# gate_wifi__bottom.net
KiCad netlist of a schematic drawn in EAGLE
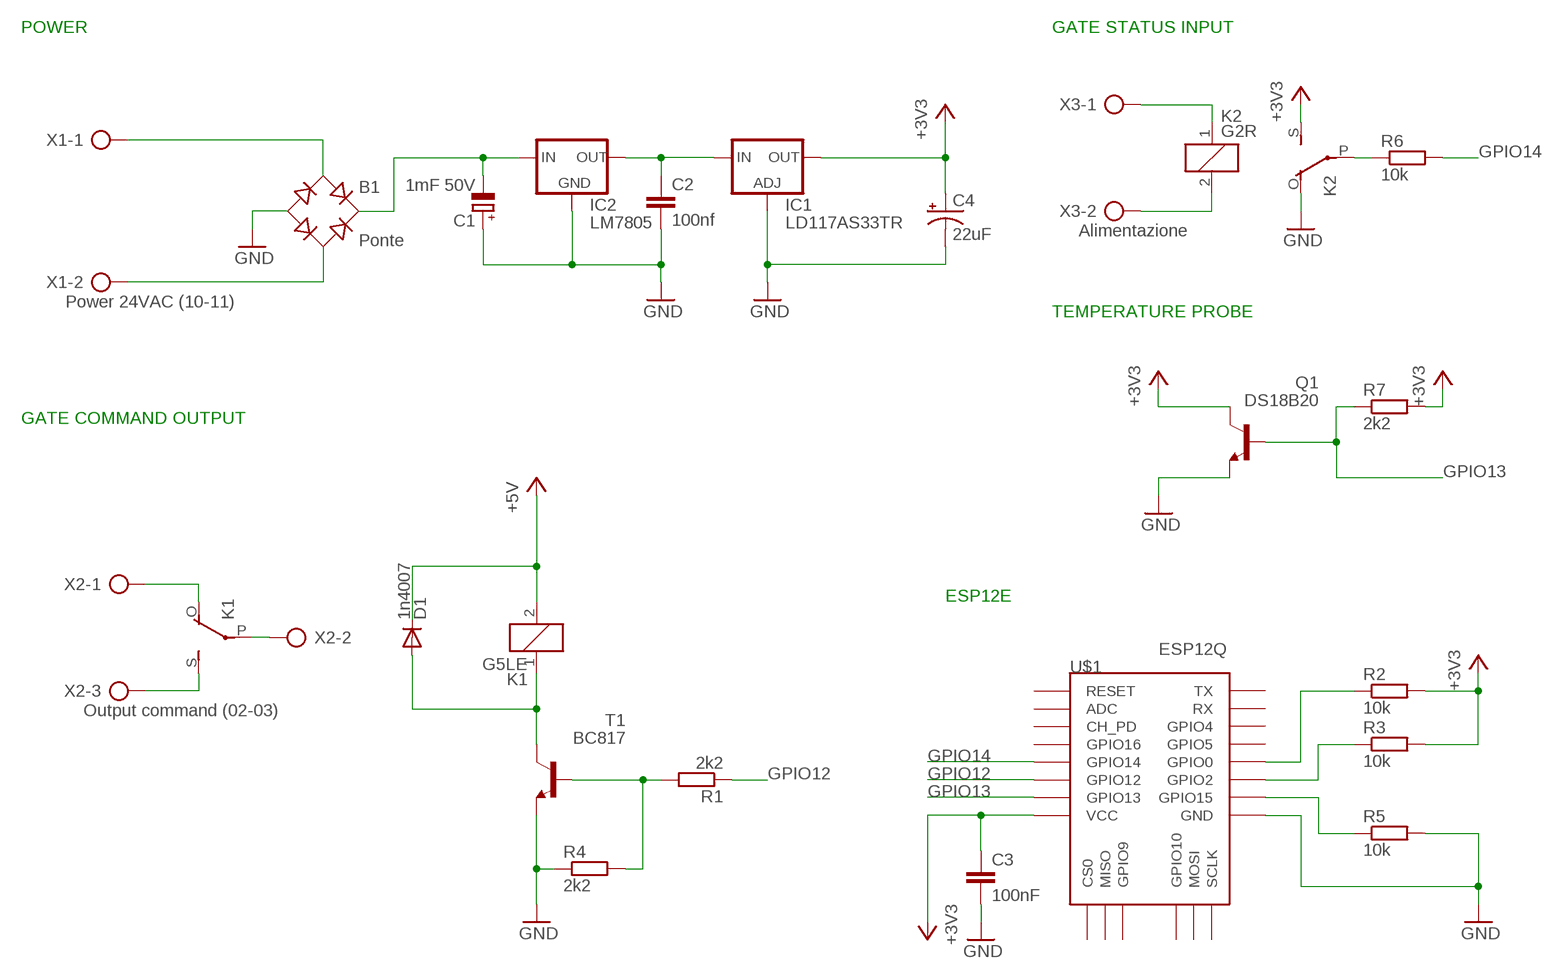
[diagram p0: schematic, sheet 1]

(export (version "E")
  (design (tool "Eeschema 10.0.6"))
  (components
    (comp (ref "B1")
      (value "Ponte")
      (footprint "eagle-import:RB1A_MOD")
      (libsource (lib "eagle-import") (part "RB1A_MODMOD"))
    )
    (comp (ref "C1")
      (value "1mF 50V")
      (footprint "eagle-import:E5-8,5")
      (libsource (lib "eagle-import") (part "CPOL-EUE5-8.5"))
    )
    (comp (ref "C2")
      (value "100nf")
      (footprint "eagle-import:C0805K")
      (libsource (lib "eagle-import") (part "C-EUC0805K"))
    )
    (comp (ref "C3")
      (value "100nF")
      (footprint "eagle-import:C0805K")
      (libsource (lib "eagle-import") (part "C-EUC0805K"))
    )
    (comp (ref "C4")
      (value "22uF")
      (footprint "eagle-import:E2,5-5")
      (libsource (lib "eagle-import") (part "CPOL-USE2.5-5"))
    )
    (comp (ref "D1")
      (value "1n4007")
      (footprint "eagle-import:DO-214AC")
      (libsource (lib "eagle-import") (part "DIODE-DO-214AC"))
    )
    (comp (ref "IC1")
      (value "LD117AS33TR")
      (footprint "eagle-import:SOT223")
      (libsource (lib "eagle-import") (part "LD117A?S33TR"))
    )
    (comp (ref "IC2")
      (value "LM7805")
      (footprint "eagle-import:78XXS")
      (libsource (lib "eagle-import") (part "78XXS"))
    )
    (comp (ref "K1")
      (value "G5LE")
      (footprint "eagle-import:G5LE")
      (libsource (lib "eagle-import") (part "G5LE"))
    )
    (comp (ref "K2")
      (value "G2R")
      (footprint "eagle-import:G2R")
      (libsource (lib "eagle-import") (part "G2R"))
    )
    (comp (ref "Q1")
      (value "DS18B20")
      (footprint "eagle-import:TO92")
      (libsource (lib "eagle-import") (part "2N3565"))
    )
    (comp (ref "R1")
      (value "2k2")
      (footprint "eagle-import:M0805")
      (libsource (lib "eagle-import") (part "R-EU_M0805"))
    )
    (comp (ref "R2")
      (value "10k")
      (footprint "eagle-import:M0805")
      (libsource (lib "eagle-import") (part "R-EU_M0805"))
    )
    (comp (ref "R3")
      (value "10k")
      (footprint "eagle-import:M0805")
      (libsource (lib "eagle-import") (part "R-EU_M0805"))
    )
    (comp (ref "R4")
      (value "2k2")
      (footprint "eagle-import:M0805")
      (libsource (lib "eagle-import") (part "R-EU_M0805"))
    )
    (comp (ref "R5")
      (value "10k")
      (footprint "eagle-import:M0805")
      (libsource (lib "eagle-import") (part "R-EU_M0805"))
    )
    (comp (ref "R6")
      (value "10k")
      (footprint "eagle-import:M0805")
      (libsource (lib "eagle-import") (part "R-EU_M0805"))
    )
    (comp (ref "R7")
      (value "2k2")
      (footprint "eagle-import:M0805")
      (libsource (lib "eagle-import") (part "R-EU_M0805"))
    )
    (comp (ref "T1")
      (value "BC817")
      (footprint "eagle-import:SOT23-BEC")
      (libsource (lib "eagle-import") (part "-NPN-SOT23-BECBC817-16LT1"))
    )
    (comp (ref "U$1")
      (value "ESP12Q")
      (footprint "eagle-import:ESP12Q")
      (libsource (lib "eagle-import") (part "ESP12Q"))
    )
    (comp (ref "X1")
      (value "Power 24VAC (10-11)")
      (footprint "eagle-import:AK500_2")
      (libsource (lib "eagle-import") (part "AK500/2"))
    )
    (comp (ref "X2")
      (value "Output command (02-03)")
      (footprint "eagle-import:AK500_3")
      (libsource (lib "eagle-import") (part "AK500/3"))
    )
    (comp (ref "X3")
      (value "Alimentazione")
      (footprint "eagle-import:AK500_2")
      (libsource (lib "eagle-import") (part "AK500/2"))
    )
  )
  (nets
    (net (code "1") (name "+3V3") (class "Default")
      (node (ref "C3") (pin "1") (pinfunction "1_1") (pintype "passive"))
      (node (ref "C4") (pin "+") (pinfunction "+_+") (pintype "passive"))
      (node (ref "IC1") (pin "4") (pinfunction "OUT_4") (pintype "passive"))
      (node (ref "K2") (pin "S") (pinfunction "S_S") (pintype "passive"))
      (node (ref "Q1") (pin "1") (pinfunction "C_1") (pintype "passive"))
      (node (ref "R2") (pin "2") (pinfunction "2_2") (pintype "passive"))
      (node (ref "R3") (pin "2") (pinfunction "2_2") (pintype "passive"))
      (node (ref "R7") (pin "2") (pinfunction "2_2") (pintype "passive"))
      (node (ref "U$1") (pin "VCC") (pinfunction "VCC_VCC") (pintype "bidirectional"))
    )
    (net (code "2") (name "+5V") (class "Default")
      (node (ref "D1") (pin "C") (pinfunction "C_C") (pintype "passive"))
      (node (ref "K1") (pin "2") (pinfunction "2_2") (pintype "passive"))
    )
    (net (code "3") (name "/GPIO12") (class "Default")
      (node (ref "R1") (pin "1") (pinfunction "1_1") (pintype "passive"))
      (node (ref "U$1") (pin "GPIO12") (pinfunction "GPIO12_GPIO12") (pintype "bidirectional"))
    )
    (net (code "4") (name "/GPIO13") (class "Default")
      (node (ref "Q1") (pin "2") (pinfunction "B_2") (pintype "passive"))
      (node (ref "R7") (pin "1") (pinfunction "1_1") (pintype "passive"))
      (node (ref "U$1") (pin "GPIO13") (pinfunction "GPIO13_GPIO13") (pintype "bidirectional"))
    )
    (net (code "5") (name "/GPIO14") (class "Default")
      (node (ref "R6") (pin "2") (pinfunction "2_2") (pintype "passive"))
      (node (ref "U$1") (pin "GPIO14") (pinfunction "GPIO14_GPIO14") (pintype "bidirectional"))
    )
    (net (code "6") (name "GND") (class "Default")
      (node (ref "B1") (pin "-") (pinfunction "-_-") (pintype "passive"))
      (node (ref "C1") (pin "+") (pinfunction "+_+") (pintype "passive"))
      (node (ref "C2") (pin "2") (pinfunction "2_2") (pintype "passive"))
      (node (ref "C3") (pin "2") (pinfunction "2_2") (pintype "passive"))
      (node (ref "C4") (pin "-") (pinfunction "-_-") (pintype "passive"))
      (node (ref "IC1") (pin "1") (pinfunction "ADJ_1") (pintype "input"))
      (node (ref "IC2") (pin "GND") (pinfunction "GND_GND") (pintype "input"))
      (node (ref "K2") (pin "O") (pinfunction "O_O") (pintype "passive"))
      (node (ref "Q1") (pin "3") (pinfunction "E_3") (pintype "passive"))
      (node (ref "R4") (pin "1") (pinfunction "1_1") (pintype "passive"))
      (node (ref "R5") (pin "2") (pinfunction "2_2") (pintype "passive"))
      (node (ref "T1") (pin "E") (pinfunction "E_E") (pintype "passive"))
      (node (ref "U$1") (pin "GND") (pinfunction "GND_GND") (pintype "bidirectional"))
    )
    (net (code "7") (name "Net-(B1-Pad+)") (class "Default")
      (node (ref "B1") (pin "+") (pinfunction "+_+") (pintype "passive"))
      (node (ref "C1") (pin "-") (pinfunction "-_-") (pintype "passive"))
      (node (ref "IC2") (pin "IN") (pinfunction "IN_IN") (pintype "input"))
    )
    (net (code "8") (name "Net-(D1-PadA)") (class "Default")
      (node (ref "D1") (pin "A") (pinfunction "A_A") (pintype "passive"))
      (node (ref "K1") (pin "1") (pinfunction "1_1") (pintype "passive"))
      (node (ref "T1") (pin "C") (pinfunction "C_C") (pintype "passive"))
    )
    (net (code "9") (name "Net-(IC1-IN)") (class "Default")
      (node (ref "C2") (pin "1") (pinfunction "1_1") (pintype "passive"))
      (node (ref "IC1") (pin "3") (pinfunction "IN_3") (pintype "input"))
      (node (ref "IC2") (pin "OUT") (pinfunction "OUT_OUT") (pintype "passive"))
    )
    (net (code "10") (name "Net-(K2-PadP)") (class "Default")
      (node (ref "K2") (pin "P") (pinfunction "P_P") (pintype "passive"))
      (node (ref "R6") (pin "1") (pinfunction "1_1") (pintype "passive"))
    )
    (net (code "11") (name "Net-(R1-Pad2)") (class "Default")
      (node (ref "R1") (pin "2") (pinfunction "2_2") (pintype "passive"))
      (node (ref "R4") (pin "2") (pinfunction "2_2") (pintype "passive"))
      (node (ref "T1") (pin "B") (pinfunction "B_B") (pintype "passive"))
    )
    (net (code "12") (name "Net-(R2-Pad1)") (class "Default")
      (node (ref "R2") (pin "1") (pinfunction "1_1") (pintype "passive"))
      (node (ref "U$1") (pin "GPIO0") (pinfunction "GPIO0_GPIO0") (pintype "bidirectional"))
    )
    (net (code "13") (name "Net-(R3-Pad1)") (class "Default")
      (node (ref "R3") (pin "1") (pinfunction "1_1") (pintype "passive"))
      (node (ref "U$1") (pin "GPIO2") (pinfunction "GPIO2_GPIO2") (pintype "bidirectional"))
    )
    (net (code "14") (name "Net-(R5-Pad1)") (class "Default")
      (node (ref "R5") (pin "1") (pinfunction "1_1") (pintype "passive"))
      (node (ref "U$1") (pin "GPIO15") (pinfunction "GPIO15_GPIO15") (pintype "bidirectional"))
    )
    (net (code "15") (name "Net-(X1A-KL)") (class "Default")
      (node (ref "B1") (pin "AC1") (pinfunction "AC1_AC1") (pintype "passive"))
      (node (ref "X1") (pin "1") (pinfunction "KL_1") (pintype "passive"))
    )
    (net (code "16") (name "Net-(X1B-KL)") (class "Default")
      (node (ref "B1") (pin "AC2") (pinfunction "AC2_AC2") (pintype "passive"))
      (node (ref "X1") (pin "2") (pinfunction "KL_2") (pintype "passive"))
    )
    (net (code "17") (name "Net-(X2A-KL)") (class "Default")
      (node (ref "K1") (pin "O") (pinfunction "O_O") (pintype "passive"))
      (node (ref "X2") (pin "1") (pinfunction "KL_1") (pintype "passive"))
    )
    (net (code "18") (name "Net-(X2B-KL)") (class "Default")
      (node (ref "K1") (pin "P") (pinfunction "P_P") (pintype "passive"))
      (node (ref "X2") (pin "2") (pinfunction "KL_2") (pintype "passive"))
    )
    (net (code "19") (name "Net-(X2C-KL)") (class "Default")
      (node (ref "K1") (pin "S") (pinfunction "S_S") (pintype "passive"))
      (node (ref "X2") (pin "3") (pinfunction "KL_3") (pintype "passive"))
    )
    (net (code "20") (name "Net-(X3A-KL)") (class "Default")
      (node (ref "K2") (pin "1") (pinfunction "1_1") (pintype "passive"))
      (node (ref "X3") (pin "1") (pinfunction "KL_1") (pintype "passive"))
    )
    (net (code "21") (name "Net-(X3B-KL)") (class "Default")
      (node (ref "K2") (pin "2") (pinfunction "2_2") (pintype "passive"))
      (node (ref "X3") (pin "2") (pinfunction "KL_2") (pintype "passive"))
    )
    (net (code "22") (name "unconnected-(U$1-PadADC)") (class "Default")
      (node (ref "U$1") (pin "ADC") (pinfunction "ADC_ADC") (pintype "bidirectional"))
    )
    (net (code "23") (name "unconnected-(U$1-PadCH_PD)") (class "Default")
      (node (ref "U$1") (pin "CH_PD") (pinfunction "CH_PD_CH_PD") (pintype "bidirectional"))
    )
    (net (code "24") (name "unconnected-(U$1-PadCS0)") (class "Default")
      (node (ref "U$1") (pin "CS0") (pinfunction "CS0_CS0") (pintype "bidirectional"))
    )
    (net (code "25") (name "unconnected-(U$1-PadGPIO4)") (class "Default")
      (node (ref "U$1") (pin "GPIO4") (pinfunction "GPIO4_GPIO4") (pintype "bidirectional"))
    )
    (net (code "26") (name "unconnected-(U$1-PadGPIO5)") (class "Default")
      (node (ref "U$1") (pin "GPIO5") (pinfunction "GPIO5_GPIO5") (pintype "bidirectional"))
    )
    (net (code "27") (name "unconnected-(U$1-PadGPIO9)") (class "Default")
      (node (ref "U$1") (pin "GPIO9") (pinfunction "GPIO9_GPIO9") (pintype "bidirectional"))
    )
    (net (code "28") (name "unconnected-(U$1-PadGPIO10)") (class "Default")
      (node (ref "U$1") (pin "GPIO10") (pinfunction "GPIO10_GPIO10") (pintype "bidirectional"))
    )
    (net (code "29") (name "unconnected-(U$1-PadGPIO16)") (class "Default")
      (node (ref "U$1") (pin "GPIO16") (pinfunction "GPIO16_GPIO16") (pintype "bidirectional"))
    )
    (net (code "30") (name "unconnected-(U$1-PadMISO)") (class "Default")
      (node (ref "U$1") (pin "MISO") (pinfunction "MISO_MISO") (pintype "bidirectional"))
    )
    (net (code "31") (name "unconnected-(U$1-PadMOSI)") (class "Default")
      (node (ref "U$1") (pin "MOSI") (pinfunction "MOSI_MOSI") (pintype "bidirectional"))
    )
    (net (code "32") (name "unconnected-(U$1-PadRESET)") (class "Default")
      (node (ref "U$1") (pin "RESET") (pinfunction "RESET_RESET") (pintype "bidirectional"))
    )
    (net (code "33") (name "unconnected-(U$1-PadRX)") (class "Default")
      (node (ref "U$1") (pin "RX") (pinfunction "RX_RX") (pintype "bidirectional"))
    )
    (net (code "34") (name "unconnected-(U$1-PadSCLK)") (class "Default")
      (node (ref "U$1") (pin "SCLK") (pinfunction "SCLK_SCLK") (pintype "bidirectional"))
    )
    (net (code "35") (name "unconnected-(U$1-PadTX)") (class "Default")
      (node (ref "U$1") (pin "TX") (pinfunction "TX_TX") (pintype "bidirectional"))
    )
  )
)
